# NorthSide.net
KiCad netlist of a schematic drawn in Altium Designer
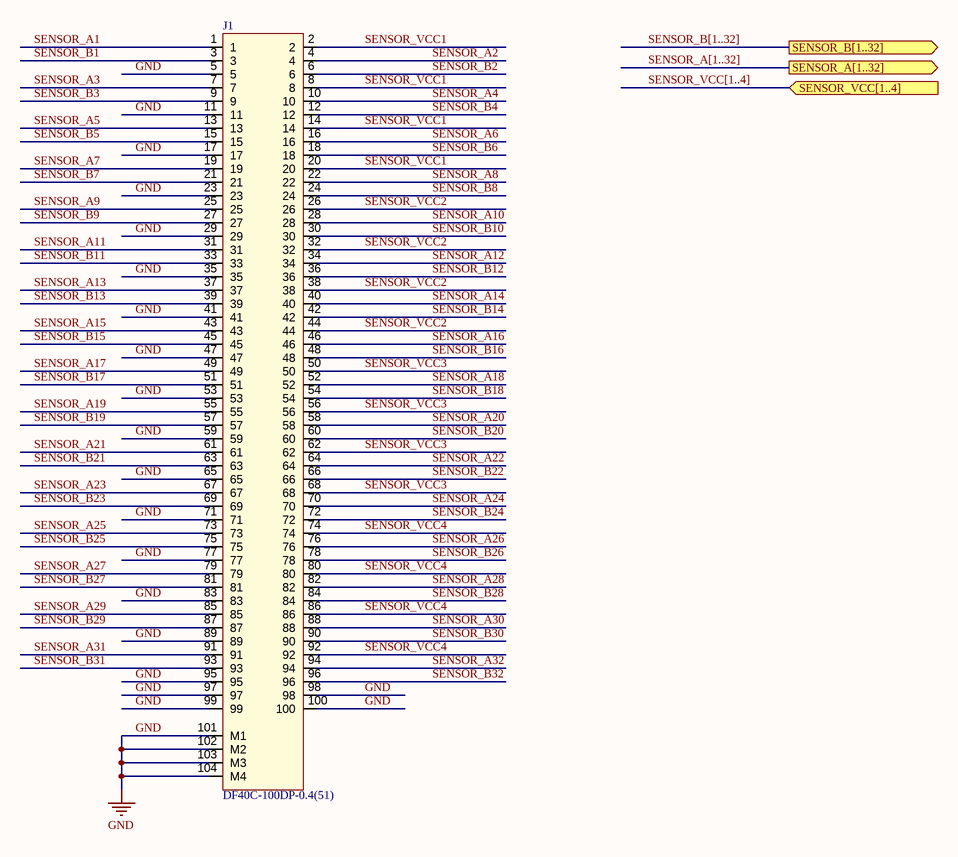
[diagram p0: NorthSide.SchDoc]

(export (version "E")
  (design (tool "Eeschema 10.0.6"))
  (components
    (comp (ref "J1")
      (value "DF40C-100DP-0.4(51)")
      (footprint "con100_hirose-df40c-100dp_129h")
      (description "CONN HDR 100POS 0.4MM SMD GOLD")
      (fields (field (name "MFG") "Hirose") (field (name "VOLTAGE") "30V"))
      (libsource (lib "SynapseLibrary") (part "DF40C-100DP-0.4(51)"))
    )
  )
  (nets
    (net (code "1") (name "/SENSOR_A1") (class "Default")
      (node (ref "J1") (pin "1") (pinfunction "1_1") (pintype "passive"))
    )
    (net (code "2") (name "/SENSOR_A2") (class "Default")
      (node (ref "J1") (pin "4") (pinfunction "4_4") (pintype "passive"))
    )
    (net (code "3") (name "/SENSOR_A3") (class "Default")
      (node (ref "J1") (pin "7") (pinfunction "7_7") (pintype "passive"))
    )
    (net (code "4") (name "/SENSOR_A4") (class "Default")
      (node (ref "J1") (pin "10") (pinfunction "10_10") (pintype "passive"))
    )
    (net (code "5") (name "/SENSOR_A5") (class "Default")
      (node (ref "J1") (pin "13") (pinfunction "13_13") (pintype "passive"))
    )
    (net (code "6") (name "/SENSOR_A6") (class "Default")
      (node (ref "J1") (pin "16") (pinfunction "16_16") (pintype "passive"))
    )
    (net (code "7") (name "/SENSOR_A7") (class "Default")
      (node (ref "J1") (pin "19") (pinfunction "19_19") (pintype "passive"))
    )
    (net (code "8") (name "/SENSOR_A8") (class "Default")
      (node (ref "J1") (pin "22") (pinfunction "22_22") (pintype "passive"))
    )
    (net (code "9") (name "/SENSOR_A9") (class "Default")
      (node (ref "J1") (pin "25") (pinfunction "25_25") (pintype "passive"))
    )
    (net (code "10") (name "/SENSOR_A10") (class "Default")
      (node (ref "J1") (pin "28") (pinfunction "28_28") (pintype "passive"))
    )
    (net (code "11") (name "/SENSOR_A11") (class "Default")
      (node (ref "J1") (pin "31") (pinfunction "31_31") (pintype "passive"))
    )
    (net (code "12") (name "/SENSOR_A12") (class "Default")
      (node (ref "J1") (pin "34") (pinfunction "34_34") (pintype "passive"))
    )
    (net (code "13") (name "/SENSOR_A13") (class "Default")
      (node (ref "J1") (pin "37") (pinfunction "37_37") (pintype "passive"))
    )
    (net (code "14") (name "/SENSOR_A14") (class "Default")
      (node (ref "J1") (pin "40") (pinfunction "40_40") (pintype "passive"))
    )
    (net (code "15") (name "/SENSOR_A15") (class "Default")
      (node (ref "J1") (pin "43") (pinfunction "43_43") (pintype "passive"))
    )
    (net (code "16") (name "/SENSOR_A16") (class "Default")
      (node (ref "J1") (pin "46") (pinfunction "46_46") (pintype "passive"))
    )
    (net (code "17") (name "/SENSOR_A17") (class "Default")
      (node (ref "J1") (pin "49") (pinfunction "49_49") (pintype "passive"))
    )
    (net (code "18") (name "/SENSOR_A18") (class "Default")
      (node (ref "J1") (pin "52") (pinfunction "52_52") (pintype "passive"))
    )
    (net (code "19") (name "/SENSOR_A19") (class "Default")
      (node (ref "J1") (pin "55") (pinfunction "55_55") (pintype "passive"))
    )
    (net (code "20") (name "/SENSOR_A20") (class "Default")
      (node (ref "J1") (pin "58") (pinfunction "58_58") (pintype "passive"))
    )
    (net (code "21") (name "/SENSOR_A21") (class "Default")
      (node (ref "J1") (pin "61") (pinfunction "61_61") (pintype "passive"))
    )
    (net (code "22") (name "/SENSOR_A22") (class "Default")
      (node (ref "J1") (pin "64") (pinfunction "64_64") (pintype "passive"))
    )
    (net (code "23") (name "/SENSOR_A23") (class "Default")
      (node (ref "J1") (pin "67") (pinfunction "67_67") (pintype "passive"))
    )
    (net (code "24") (name "/SENSOR_A24") (class "Default")
      (node (ref "J1") (pin "70") (pinfunction "70_70") (pintype "passive"))
    )
    (net (code "25") (name "/SENSOR_A25") (class "Default")
      (node (ref "J1") (pin "73") (pinfunction "73_73") (pintype "passive"))
    )
    (net (code "26") (name "/SENSOR_A26") (class "Default")
      (node (ref "J1") (pin "76") (pinfunction "76_76") (pintype "passive"))
    )
    (net (code "27") (name "/SENSOR_A27") (class "Default")
      (node (ref "J1") (pin "79") (pinfunction "79_79") (pintype "passive"))
    )
    (net (code "28") (name "/SENSOR_A28") (class "Default")
      (node (ref "J1") (pin "82") (pinfunction "82_82") (pintype "passive"))
    )
    (net (code "29") (name "/SENSOR_A29") (class "Default")
      (node (ref "J1") (pin "85") (pinfunction "85_85") (pintype "passive"))
    )
    (net (code "30") (name "/SENSOR_A30") (class "Default")
      (node (ref "J1") (pin "88") (pinfunction "88_88") (pintype "passive"))
    )
    (net (code "31") (name "/SENSOR_A31") (class "Default")
      (node (ref "J1") (pin "91") (pinfunction "91_91") (pintype "passive"))
    )
    (net (code "32") (name "/SENSOR_A32") (class "Default")
      (node (ref "J1") (pin "94") (pinfunction "94_94") (pintype "passive"))
    )
    (net (code "34") (name "/SENSOR_B1") (class "Default")
      (node (ref "J1") (pin "3") (pinfunction "3_3") (pintype "passive"))
    )
    (net (code "35") (name "/SENSOR_B2") (class "Default")
      (node (ref "J1") (pin "6") (pinfunction "6_6") (pintype "passive"))
    )
    (net (code "36") (name "/SENSOR_B3") (class "Default")
      (node (ref "J1") (pin "9") (pinfunction "9_9") (pintype "passive"))
    )
    (net (code "37") (name "/SENSOR_B4") (class "Default")
      (node (ref "J1") (pin "12") (pinfunction "12_12") (pintype "passive"))
    )
    (net (code "38") (name "/SENSOR_B5") (class "Default")
      (node (ref "J1") (pin "15") (pinfunction "15_15") (pintype "passive"))
    )
    (net (code "39") (name "/SENSOR_B6") (class "Default")
      (node (ref "J1") (pin "18") (pinfunction "18_18") (pintype "passive"))
    )
    (net (code "40") (name "/SENSOR_B7") (class "Default")
      (node (ref "J1") (pin "21") (pinfunction "21_21") (pintype "passive"))
    )
    (net (code "41") (name "/SENSOR_B8") (class "Default")
      (node (ref "J1") (pin "24") (pinfunction "24_24") (pintype "passive"))
    )
    (net (code "42") (name "/SENSOR_B9") (class "Default")
      (node (ref "J1") (pin "27") (pinfunction "27_27") (pintype "passive"))
    )
    (net (code "43") (name "/SENSOR_B10") (class "Default")
      (node (ref "J1") (pin "30") (pinfunction "30_30") (pintype "passive"))
    )
    (net (code "44") (name "/SENSOR_B11") (class "Default")
      (node (ref "J1") (pin "33") (pinfunction "33_33") (pintype "passive"))
    )
    (net (code "45") (name "/SENSOR_B12") (class "Default")
      (node (ref "J1") (pin "36") (pinfunction "36_36") (pintype "passive"))
    )
    (net (code "46") (name "/SENSOR_B13") (class "Default")
      (node (ref "J1") (pin "39") (pinfunction "39_39") (pintype "passive"))
    )
    (net (code "47") (name "/SENSOR_B14") (class "Default")
      (node (ref "J1") (pin "42") (pinfunction "42_42") (pintype "passive"))
    )
    (net (code "48") (name "/SENSOR_B15") (class "Default")
      (node (ref "J1") (pin "45") (pinfunction "45_45") (pintype "passive"))
    )
    (net (code "49") (name "/SENSOR_B16") (class "Default")
      (node (ref "J1") (pin "48") (pinfunction "48_48") (pintype "passive"))
    )
    (net (code "50") (name "/SENSOR_B17") (class "Default")
      (node (ref "J1") (pin "51") (pinfunction "51_51") (pintype "passive"))
    )
    (net (code "51") (name "/SENSOR_B18") (class "Default")
      (node (ref "J1") (pin "54") (pinfunction "54_54") (pintype "passive"))
    )
    (net (code "52") (name "/SENSOR_B19") (class "Default")
      (node (ref "J1") (pin "57") (pinfunction "57_57") (pintype "passive"))
    )
    (net (code "53") (name "/SENSOR_B20") (class "Default")
      (node (ref "J1") (pin "60") (pinfunction "60_60") (pintype "passive"))
    )
    (net (code "54") (name "/SENSOR_B21") (class "Default")
      (node (ref "J1") (pin "63") (pinfunction "63_63") (pintype "passive"))
    )
    (net (code "55") (name "/SENSOR_B22") (class "Default")
      (node (ref "J1") (pin "66") (pinfunction "66_66") (pintype "passive"))
    )
    (net (code "56") (name "/SENSOR_B23") (class "Default")
      (node (ref "J1") (pin "69") (pinfunction "69_69") (pintype "passive"))
    )
    (net (code "57") (name "/SENSOR_B24") (class "Default")
      (node (ref "J1") (pin "72") (pinfunction "72_72") (pintype "passive"))
    )
    (net (code "58") (name "/SENSOR_B25") (class "Default")
      (node (ref "J1") (pin "75") (pinfunction "75_75") (pintype "passive"))
    )
    (net (code "59") (name "/SENSOR_B26") (class "Default")
      (node (ref "J1") (pin "78") (pinfunction "78_78") (pintype "passive"))
    )
    (net (code "60") (name "/SENSOR_B27") (class "Default")
      (node (ref "J1") (pin "81") (pinfunction "81_81") (pintype "passive"))
    )
    (net (code "61") (name "/SENSOR_B28") (class "Default")
      (node (ref "J1") (pin "84") (pinfunction "84_84") (pintype "passive"))
    )
    (net (code "62") (name "/SENSOR_B29") (class "Default")
      (node (ref "J1") (pin "87") (pinfunction "87_87") (pintype "passive"))
    )
    (net (code "63") (name "/SENSOR_B30") (class "Default")
      (node (ref "J1") (pin "90") (pinfunction "90_90") (pintype "passive"))
    )
    (net (code "64") (name "/SENSOR_B31") (class "Default")
      (node (ref "J1") (pin "93") (pinfunction "93_93") (pintype "passive"))
    )
    (net (code "65") (name "/SENSOR_B32") (class "Default")
      (node (ref "J1") (pin "96") (pinfunction "96_96") (pintype "passive"))
    )
    (net (code "67") (name "/SENSOR_VCC1") (class "Default")
      (node (ref "J1") (pin "14") (pinfunction "14_14") (pintype "passive"))
      (node (ref "J1") (pin "2") (pinfunction "2_2") (pintype "passive"))
      (node (ref "J1") (pin "20") (pinfunction "20_20") (pintype "passive"))
      (node (ref "J1") (pin "8") (pinfunction "8_8") (pintype "passive"))
    )
    (net (code "68") (name "/SENSOR_VCC2") (class "Default")
      (node (ref "J1") (pin "26") (pinfunction "26_26") (pintype "passive"))
      (node (ref "J1") (pin "32") (pinfunction "32_32") (pintype "passive"))
      (node (ref "J1") (pin "38") (pinfunction "38_38") (pintype "passive"))
      (node (ref "J1") (pin "44") (pinfunction "44_44") (pintype "passive"))
    )
    (net (code "69") (name "/SENSOR_VCC3") (class "Default")
      (node (ref "J1") (pin "50") (pinfunction "50_50") (pintype "passive"))
      (node (ref "J1") (pin "56") (pinfunction "56_56") (pintype "passive"))
      (node (ref "J1") (pin "62") (pinfunction "62_62") (pintype "passive"))
      (node (ref "J1") (pin "68") (pinfunction "68_68") (pintype "passive"))
    )
    (net (code "70") (name "/SENSOR_VCC4") (class "Default")
      (node (ref "J1") (pin "74") (pinfunction "74_74") (pintype "passive"))
      (node (ref "J1") (pin "80") (pinfunction "80_80") (pintype "passive"))
      (node (ref "J1") (pin "86") (pinfunction "86_86") (pintype "passive"))
      (node (ref "J1") (pin "92") (pinfunction "92_92") (pintype "passive"))
    )
    (net (code "72") (name "GND") (class "Default")
      (node (ref "J1") (pin "100") (pinfunction "100_100") (pintype "passive"))
      (node (ref "J1") (pin "101") (pinfunction "M1_101") (pintype "passive"))
      (node (ref "J1") (pin "102") (pinfunction "M2_102") (pintype "passive"))
      (node (ref "J1") (pin "103") (pinfunction "M3_103") (pintype "passive"))
      (node (ref "J1") (pin "104") (pinfunction "M4_104") (pintype "passive"))
      (node (ref "J1") (pin "11") (pinfunction "11_11") (pintype "passive"))
      (node (ref "J1") (pin "17") (pinfunction "17_17") (pintype "passive"))
      (node (ref "J1") (pin "23") (pinfunction "23_23") (pintype "passive"))
      (node (ref "J1") (pin "29") (pinfunction "29_29") (pintype "passive"))
      (node (ref "J1") (pin "35") (pinfunction "35_35") (pintype "passive"))
      (node (ref "J1") (pin "41") (pinfunction "41_41") (pintype "passive"))
      (node (ref "J1") (pin "47") (pinfunction "47_47") (pintype "passive"))
      (node (ref "J1") (pin "5") (pinfunction "5_5") (pintype "passive"))
      (node (ref "J1") (pin "53") (pinfunction "53_53") (pintype "passive"))
      (node (ref "J1") (pin "59") (pinfunction "59_59") (pintype "passive"))
      (node (ref "J1") (pin "65") (pinfunction "65_65") (pintype "passive"))
      (node (ref "J1") (pin "71") (pinfunction "71_71") (pintype "passive"))
      (node (ref "J1") (pin "77") (pinfunction "77_77") (pintype "passive"))
      (node (ref "J1") (pin "83") (pinfunction "83_83") (pintype "passive"))
      (node (ref "J1") (pin "89") (pinfunction "89_89") (pintype "passive"))
      (node (ref "J1") (pin "95") (pinfunction "95_95") (pintype "passive"))
      (node (ref "J1") (pin "97") (pinfunction "97_97") (pintype "passive"))
      (node (ref "J1") (pin "98") (pinfunction "98_98") (pintype "passive"))
      (node (ref "J1") (pin "99") (pinfunction "99_99") (pintype "passive"))
    )
  )
)
